# Microcontroller.net
KiCad netlist of a schematic drawn in Altium Designer
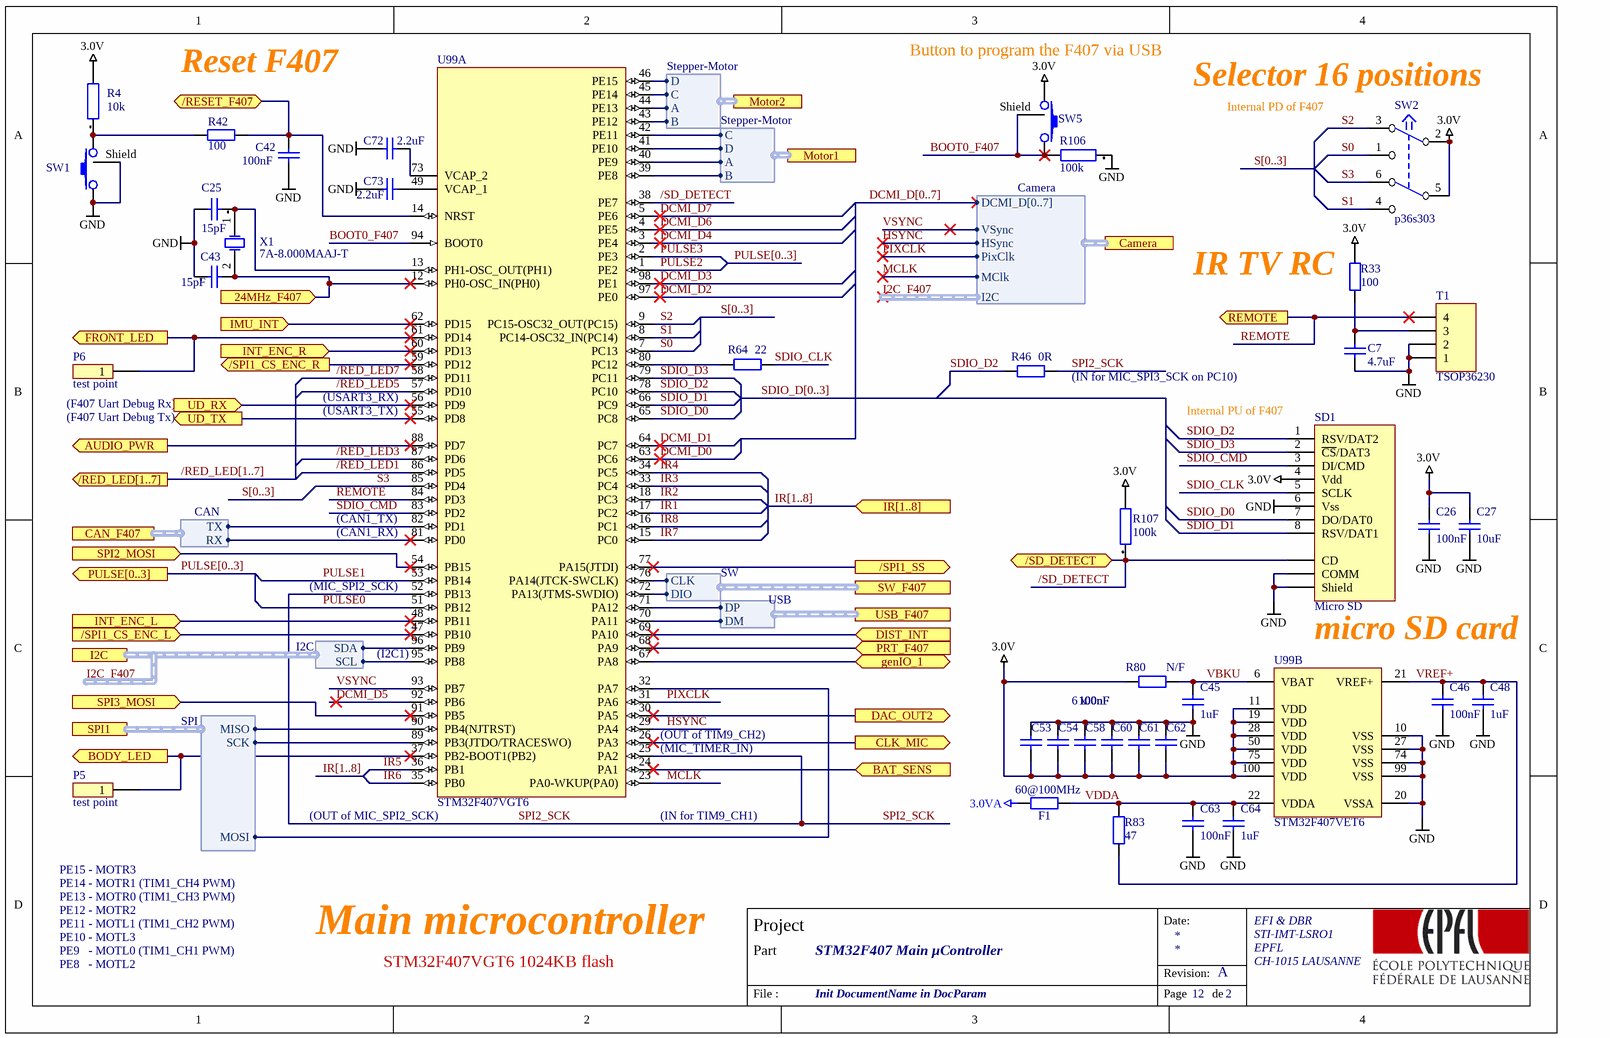
[diagram p0: Microcontroller.SchDoc]

(export (version "E")
  (design (tool "Eeschema 10.0.6"))
  (components
    (comp (ref "C7")
      (value "4.7uF")
      (footprint "ROB_0603")
      (description "Capacitor")
      (fields (field (name "PUBLISHER") "Altium Limited"))
      (libsource (lib "Miscellaneous Devices") (part "Cap"))
    )
    (comp (ref "C25")
      (value "15pF")
      (footprint "ROB_0603")
      (description "Capacitor")
      (fields (field (name "MANUFACTURER") "Phycomp") (field (name "VOLTAGE") "50"))
      (libsource (lib "LSRO1Altium") (part "CAP-NP"))
    )
    (comp (ref "C26")
      (value "100nF")
      (footprint "ROB_0603")
      (description "Capacitor")
      (fields (field (name "PUBLISHER") "Altium Limited"))
      (libsource (lib "Rob_sch") (part "Cap"))
    )
    (comp (ref "C27")
      (value "10uF")
      (footprint "ROB_0603")
      (description "Capacitor")
      (fields (field (name "PUBLISHER") "Altium Limited"))
      (libsource (lib "Rob_sch") (part "Cap"))
    )
    (comp (ref "C42")
      (value "100nF")
      (footprint "ROB_0603")
      (description "Capacitor")
      (fields (field (name "PUBLISHER") "Altium Limited"))
      (libsource (lib "Rob_sch") (part "Cap"))
    )
    (comp (ref "C43")
      (value "15pF")
      (footprint "ROB_0603")
      (description "Capacitor")
      (fields (field (name "MANUFACTURER") "Phycomp") (field (name "VOLTAGE") "50"))
      (libsource (lib "LSRO1Altium") (part "CAP-NP"))
    )
    (comp (ref "C45")
      (value "1uF")
      (footprint "ROB_0603")
      (description "Capacitor")
      (fields (field (name "PUBLISHER") "Altium Limited"))
      (libsource (lib "Rob_sch") (part "Cap"))
    )
    (comp (ref "C46")
      (value "100nF")
      (footprint "ROB_0603")
      (description "Capacitor")
      (fields (field (name "PUBLISHER") "Altium Limited"))
      (libsource (lib "Rob_sch") (part "Cap"))
    )
    (comp (ref "C48")
      (value "1uF")
      (footprint "ROB_0603")
      (description "Capacitor")
      (fields (field (name "PUBLISHER") "Altium Limited"))
      (libsource (lib "Rob_sch") (part "Cap"))
    )
    (comp (ref "C53")
      (value "100nF")
      (footprint "ROB_0603")
      (description "Capacitor")
      (fields (field (name "PUBLISHER") "Altium Limited"))
      (libsource (lib "Rob_sch") (part "Cap"))
    )
    (comp (ref "C54")
      (value "100nF")
      (footprint "ROB_0603")
      (description "Capacitor")
      (fields (field (name "PUBLISHER") "Altium Limited"))
      (libsource (lib "Rob_sch") (part "Cap"))
    )
    (comp (ref "C58")
      (value "100nF")
      (footprint "ROB_0603")
      (description "Capacitor")
      (fields (field (name "PUBLISHER") "Altium Limited"))
      (libsource (lib "Rob_sch") (part "Cap"))
    )
    (comp (ref "C60")
      (value "100nF")
      (footprint "ROB_0603")
      (description "Capacitor")
      (fields (field (name "PUBLISHER") "Altium Limited"))
      (libsource (lib "Rob_sch") (part "Cap"))
    )
    (comp (ref "C61")
      (value "100nF")
      (footprint "ROB_0603")
      (description "Capacitor")
      (fields (field (name "PUBLISHER") "Altium Limited"))
      (libsource (lib "Rob_sch") (part "Cap"))
    )
    (comp (ref "C62")
      (value "100nF")
      (footprint "ROB_0603")
      (description "Capacitor")
      (fields (field (name "PUBLISHER") "Altium Limited"))
      (libsource (lib "Rob_sch") (part "Cap"))
    )
    (comp (ref "C63")
      (value "100nF")
      (footprint "ROB_0603")
      (description "Capacitor")
      (fields (field (name "PUBLISHER") "Altium Limited"))
      (libsource (lib "Rob_sch") (part "Cap"))
    )
    (comp (ref "C64")
      (value "1uF")
      (footprint "ROB_0603")
      (description "Capacitor")
      (fields (field (name "PUBLISHER") "Altium Limited"))
      (libsource (lib "Rob_sch") (part "Cap"))
    )
    (comp (ref "C72")
      (value "2.2uF")
      (footprint "ROB_0603")
      (description "Capacitor")
      (fields (field (name "PUBLISHER") "Altium Limited"))
      (libsource (lib "Rob_sch") (part "Cap"))
    )
    (comp (ref "C73")
      (value "2.2uF")
      (footprint "ROB_0603")
      (description "Capacitor")
      (fields (field (name "PUBLISHER") "Altium Limited"))
      (libsource (lib "Rob_sch") (part "Cap"))
    )
    (comp (ref "F1")
      (value "60@100MHz")
      (footprint "rob_0603")
      (description "Bead Ferrite")
      (libsource (lib "ASLCommonLibrarySch_1.00") (part "RES_0603"))
    )
    (comp (ref "P5")
      (value "test point")
      (footprint "testpoint")
      (description "Header, 1-Pin,  bottom")
      (fields (field (name "MANUFACTURER") "Generic Components") (field (name "PUBLISHER") "Altium Limited"))
      (libsource (lib "Rob_sch") (part "Header 1"))
    )
    (comp (ref "P6")
      (value "test point")
      (footprint "testpoint")
      (description "Header, 1-Pin,  bottom")
      (fields (field (name "MANUFACTURER") "Generic Components") (field (name "PUBLISHER") "Altium Limited"))
      (libsource (lib "Rob_sch") (part "Header 1"))
    )
    (comp (ref "R4")
      (value "10k")
      (footprint "ROB_0603")
      (description "Resistor")
      (fields (field (name "TOLERANCE") "+/-1") (field (name "MANUFACTURER") "Multicomp"))
      (libsource (lib "LSRO1Altium") (part "RES"))
    )
    (comp (ref "R33")
      (value "100")
      (footprint "ROB_0603")
      (description "Resistor")
      (fields (field (name "PUBLISHER") "Altium Limited"))
      (libsource (lib "") (part "Res2_1"))
    )
    (comp (ref "R42")
      (value "100")
      (footprint "ROB_0603")
      (description "Resistor")
      (fields (field (name "PUBLISHER") "Altium Limited"))
      (libsource (lib "") (part "Res2_1"))
    )
    (comp (ref "R46")
      (value "0R")
      (footprint "ROB_0603")
      (description "Resistor")
      (fields (field (name "PUBLISHER") "Altium Limited"))
      (libsource (lib "Miscellaneous Devices") (part "Res2"))
    )
    (comp (ref "R64")
      (value "22")
      (footprint "ROB_0603")
      (description "Resistor")
      (fields (field (name "PUBLISHER") "Altium Limited"))
      (libsource (lib "Miscellaneous Devices") (part "Res2"))
    )
    (comp (ref "R80")
      (value "N/F")
      (footprint "ROB_0603")
      (description "Resistor")
      (fields (field (name "PUBLISHER") "Altium Limited"))
      (libsource (lib "Miscellaneous Devices") (part "Res2"))
    )
    (comp (ref "R83")
      (value "47")
      (footprint "ROB_0603")
      (description "Resistor")
      (fields (field (name "PUBLISHER") "Altium Limited"))
      (libsource (lib "") (part "Res2_2"))
    )
    (comp (ref "R106")
      (value "100k")
      (footprint "ROB_0603")
      (description "Resistor")
      (fields (field (name "TOLERANCE") "+/-1") (field (name "MANUFACTURER") "Multicomp"))
      (libsource (lib "LSRO1Altium") (part "RES"))
    )
    (comp (ref "R107")
      (value "100k")
      (footprint "ROB_0603")
      (description "Resistor")
      (fields (field (name "TOLERANCE") "+/-1") (field (name "MANUFACTURER") "Multicomp"))
      (libsource (lib "LSRO1Altium") (part "RES"))
    )
    (comp (ref "SD1")
      (value "Micro SD")
      (footprint "MicroSD_DM3AT-SF-PEJM5")
      (description "uSD Connector HRS DM3AT-SF-PEJM5")
      (fields (field (name "MANUFACTURER") "Generic Components") (field (name "PUBLISHER") "Altium Limited"))
      (libsource (lib "Rob_sch") (part "CON Micro SD DM3AT-SF-PEJM5"))
    )
    (comp (ref "SW1")
      (value "button")
      (footprint "C&K_KMR2")
      (description "KMR221GLFS")
      (fields (field (name "MANUFACTURER") "Tyco"))
      (libsource (lib "Dev_Card_Lib") (part "C&K KMR2"))
    )
    (comp (ref "SW2")
      (value "p36s303")
      (footprint "p36s")
      (description "hex selector")
      (libsource (lib "Perso_sch") (part "MB2061"))
    )
    (comp (ref "SW5")
      (value "button")
      (footprint "C&K_KMR2")
      (description "KMR221GLFS")
      (fields (field (name "MANUFACTURER") "Tyco"))
      (libsource (lib "Dev_Card_Lib") (part "C&K KMR2"))
    )
    (comp (ref "T1")
      (value "TSOP36230")
      (footprint "TSOP36230")
      (description "IT TV receiver")
      (fields (field (name "PUBLISHER") "Altium Limited"))
      (libsource (lib "Miscellaneous Connectors") (part "Header 4"))
    )
    (comp (ref "U99")
      (value "STM32F407VGT6")
      (footprint "STM-LQFP100_N")
      (fields (field (name "MANUFACTURER") "STMicroelectronics") (field (name "PARTNUMBER") "STM32F407VET6"))
      (libsource (lib "") (part "STM32F407VET6_1"))
    )
    (comp (ref "X1")
      (value "7A-8.000MAAJ-T")
      (footprint "Crystal 8MHz 3.2x5mm-7A-8.000MAAJ-T")
      (description "CRYSTAL 8.0000MHZ 18PF SMD")
      (fields
        (field (name "MANUFACTURER") "TXC CORPORATION")
        (field (name "MANUFACTURER PART NUMBER") "7A-8.000MAAJ-T*")
      )
      (libsource (lib "Dev_Card_Lib") (part "7A-8.000MAAJ-T"))
    )
  )
  (nets
    (net (code "16") (name "/24MHz_F407") (class "Default")
      (node (ref "C43") (pin "2") (pinfunction "2_2") (pintype "passive"))
      (node (ref "U99") (pin "12") (pinfunction "PH0-OSC_IN(PH0)_12") (pintype "bidirectional"))
      (node (ref "X1") (pin "2") (pinfunction "OSC2_2") (pintype "passive"))
    )
    (net (code "17") (name "/AUDIO_PWR") (class "Default")
      (node (ref "U99") (pin "88") (pinfunction "PD7_88") (pintype "bidirectional+no_connect"))
    )
    (net (code "18") (name "/BAT_SENS") (class "Default")
      (node (ref "U99") (pin "24") (pinfunction "PA1_24") (pintype "bidirectional+no_connect"))
    )
    (net (code "19") (name "/BODY_LED") (class "Default")
      (node (ref "P5") (pin "1") (pinfunction "1_1") (pintype "passive"))
      (node (ref "U99") (pin "37") (pinfunction "PB2-BOOT1(PB2)_37") (pintype "bidirectional"))
    )
    (net (code "20") (name "/BOOT0_F407") (class "Default")
      (node (ref "R106") (pin "2") (pinfunction "2_2") (pintype "passive"))
      (node (ref "SW5") (pin "1") (pintype "passive"))
      (node (ref "SW5") (pin "Shield") (pinfunction "Shield_Shield") (pintype "passive"))
      (node (ref "U99") (pin "94") (pinfunction "BOOT0_94") (pintype "input"))
    )
    (net (code "21") (name "/CLK") (class "Default")
      (node (ref "U99") (pin "76") (pinfunction "PA14(JTCK-SWCLK)_76") (pintype "bidirectional"))
    )
    (net (code "22") (name "/CLK_MIC") (class "Default")
      (node (ref "U99") (pin "26") (pinfunction "PA3_26") (pintype "bidirectional+no_connect"))
    )
    (net (code "24") (name "/DAC_OUT2") (class "Default")
      (node (ref "U99") (pin "30") (pinfunction "PA5_30") (pintype "bidirectional+no_connect"))
    )
    (net (code "33") (name "/DCMI_D0") (class "Default")
      (node (ref "U99") (pin "63") (pinfunction "PC6_63") (pintype "bidirectional"))
    )
    (net (code "34") (name "/DCMI_D1") (class "Default")
      (node (ref "U99") (pin "64") (pinfunction "PC7_64") (pintype "bidirectional"))
    )
    (net (code "35") (name "/DCMI_D2") (class "Default")
      (node (ref "U99") (pin "97") (pinfunction "PE0_97") (pintype "bidirectional"))
    )
    (net (code "36") (name "/DCMI_D3") (class "Default")
      (node (ref "U99") (pin "98") (pinfunction "PE1_98") (pintype "bidirectional"))
    )
    (net (code "37") (name "/DCMI_D4") (class "Default")
      (node (ref "U99") (pin "3") (pinfunction "PE4_3") (pintype "bidirectional"))
    )
    (net (code "38") (name "/DCMI_D5") (class "Default")
      (node (ref "U99") (pin "92") (pinfunction "PB6_92") (pintype "bidirectional"))
    )
    (net (code "40") (name "/DCMI_D6") (class "Default")
      (node (ref "U99") (pin "4") (pinfunction "PE5_4") (pintype "bidirectional"))
    )
    (net (code "41") (name "/DCMI_D7") (class "Default")
      (node (ref "U99") (pin "5") (pinfunction "PE6_5") (pintype "bidirectional"))
    )
    (net (code "42") (name "/DIO") (class "Default")
      (node (ref "U99") (pin "72") (pinfunction "PA13(JTMS-SWDIO)_72") (pintype "bidirectional"))
    )
    (net (code "43") (name "/DIST_INT") (class "Default")
      (node (ref "U99") (pin "69") (pinfunction "PA10_69") (pintype "bidirectional+no_connect"))
    )
    (net (code "44") (name "/DM") (class "Default")
      (node (ref "U99") (pin "70") (pinfunction "PA11_70") (pintype "bidirectional"))
    )
    (net (code "45") (name "/DP") (class "Default")
      (node (ref "U99") (pin "71") (pinfunction "PA12_71") (pintype "bidirectional"))
    )
    (net (code "46") (name "/FRONT_LED") (class "Default")
      (node (ref "P6") (pin "1") (pinfunction "1_1") (pintype "passive"))
      (node (ref "U99") (pin "61") (pinfunction "PD14_61") (pintype "bidirectional"))
    )
    (net (code "47") (name "/HSYNC") (class "Default")
      (node (ref "U99") (pin "29") (pinfunction "PA4_29") (pintype "bidirectional+no_connect"))
    )
    (net (code "48") (name "/IMU_INT") (class "Default")
      (node (ref "U99") (pin "62") (pinfunction "PD15_62") (pintype "bidirectional+no_connect"))
    )
    (net (code "49") (name "/INT_ENC_L") (class "Default")
      (node (ref "U99") (pin "48") (pinfunction "PB11_48") (pintype "bidirectional+no_connect"))
    )
    (net (code "50") (name "/INT_ENC_R") (class "Default")
      (node (ref "U99") (pin "60") (pinfunction "PD13_60") (pintype "bidirectional+no_connect"))
    )
    (net (code "52") (name "/IR1") (class "Default")
      (node (ref "U99") (pin "17") (pinfunction "PC2_17") (pintype "bidirectional"))
    )
    (net (code "53") (name "/IR2") (class "Default")
      (node (ref "U99") (pin "18") (pinfunction "PC3_18") (pintype "bidirectional"))
    )
    (net (code "54") (name "/IR3") (class "Default")
      (node (ref "U99") (pin "33") (pinfunction "PC4_33") (pintype "bidirectional"))
    )
    (net (code "55") (name "/IR4") (class "Default")
      (node (ref "U99") (pin "34") (pinfunction "PC5_34") (pintype "bidirectional"))
    )
    (net (code "56") (name "/IR5") (class "Default")
      (node (ref "U99") (pin "36") (pinfunction "PB1_36") (pintype "bidirectional"))
    )
    (net (code "57") (name "/IR6") (class "Default")
      (node (ref "U99") (pin "35") (pinfunction "PB0_35") (pintype "bidirectional"))
    )
    (net (code "58") (name "/IR7") (class "Default")
      (node (ref "U99") (pin "15") (pinfunction "PC0_15") (pintype "bidirectional"))
    )
    (net (code "59") (name "/IR8") (class "Default")
      (node (ref "U99") (pin "16") (pinfunction "PC1_16") (pintype "bidirectional"))
    )
    (net (code "60") (name "/MCLK") (class "Default")
      (node (ref "U99") (pin "23") (pinfunction "PA0-WKUP(PA0)_23") (pintype "bidirectional+no_connect"))
    )
    (net (code "62") (name "/MISO") (class "Default")
      (node (ref "U99") (pin "90") (pinfunction "PB4(NJTRST)_90") (pintype "bidirectional"))
    )
    (net (code "63") (name "/MOSI") (class "Default")
      (node (ref "U99") (pin "32") (pinfunction "PA7_32") (pintype "bidirectional"))
    )
    (net (code "64") (name "/PIXCLK") (class "Default")
      (node (ref "U99") (pin "31") (pinfunction "PA6_31") (pintype "bidirectional+no_connect"))
    )
    (net (code "65") (name "/PRT_F407") (class "Default")
      (node (ref "U99") (pin "68") (pinfunction "PA9_68") (pintype "bidirectional+no_connect"))
    )
    (net (code "66") (name "/PULSE0") (class "Default")
      (node (ref "U99") (pin "51") (pinfunction "PB12_51") (pintype "bidirectional"))
    )
    (net (code "67") (name "/PULSE1") (class "Default")
      (node (ref "U99") (pin "53") (pinfunction "PB14_53") (pintype "bidirectional"))
    )
    (net (code "68") (name "/PULSE2") (class "Default")
      (node (ref "U99") (pin "1") (pinfunction "PE2_1") (pintype "bidirectional"))
    )
    (net (code "69") (name "/PULSE3") (class "Default")
      (node (ref "U99") (pin "2") (pinfunction "PE3_2") (pintype "bidirectional"))
    )
    (net (code "70") (name "/REMOTE") (class "Default")
      (node (ref "T1") (pin "4") (pinfunction "4_4") (pintype "passive"))
      (node (ref "U99") (pin "84") (pinfunction "PD3_84") (pintype "bidirectional"))
    )
    (net (code "71") (name "/RX") (class "Default")
      (node (ref "U99") (pin "81") (pinfunction "PD0_81") (pintype "bidirectional+no_connect"))
    )
    (net (code "72") (name "/S0") (class "Default")
      (node (ref "SW2") (pin "1") (pinfunction "NO1_1") (pintype "passive"))
      (node (ref "U99") (pin "7") (pinfunction "PC13_7") (pintype "bidirectional"))
    )
    (net (code "73") (name "/S1") (class "Default")
      (node (ref "SW2") (pin "4") (pinfunction "NO2_4") (pintype "passive"))
      (node (ref "U99") (pin "8") (pinfunction "PC14-OSC32_IN(PC14)_8") (pintype "bidirectional"))
    )
    (net (code "74") (name "/S2") (class "Default")
      (node (ref "SW2") (pin "3") (pinfunction "NC1_3") (pintype "passive"))
      (node (ref "U99") (pin "9") (pinfunction "PC15-OSC32_OUT(PC15)_9") (pintype "bidirectional"))
    )
    (net (code "75") (name "/S3") (class "Default")
      (node (ref "SW2") (pin "6") (pinfunction "NC2_6") (pintype "passive"))
      (node (ref "U99") (pin "85") (pinfunction "PD4_85") (pintype "bidirectional"))
    )
    (net (code "76") (name "/SCK") (class "Default")
      (node (ref "U99") (pin "89") (pinfunction "PB3(JTDO/TRACESWO)_89") (pintype "bidirectional"))
    )
    (net (code "78") (name "/SCL") (class "Default")
      (node (ref "U99") (pin "95") (pinfunction "PB8_95") (pintype "bidirectional"))
    )
    (net (code "79") (name "/SDA") (class "Default")
      (node (ref "U99") (pin "96") (pinfunction "PB9_96") (pintype "bidirectional"))
    )
    (net (code "80") (name "/SDIO_CLK") (class "Default")
      (node (ref "R64") (pin "1") (pinfunction "1_1") (pintype "passive"))
      (node (ref "SD1") (pin "5") (pinfunction "SCLK_5") (pintype "passive"))
    )
    (net (code "82") (name "/SDIO_CMD") (class "Default")
      (node (ref "SD1") (pin "3") (pinfunction "DI/CMD_3") (pintype "passive"))
      (node (ref "U99") (pin "83") (pinfunction "PD2_83") (pintype "bidirectional"))
    )
    (net (code "83") (name "/SDIO_D0") (class "Default")
      (node (ref "SD1") (pin "7") (pinfunction "DO/DAT0_7") (pintype "passive"))
      (node (ref "U99") (pin "65") (pinfunction "PC8_65") (pintype "bidirectional"))
    )
    (net (code "84") (name "/SDIO_D1") (class "Default")
      (node (ref "SD1") (pin "8") (pinfunction "RSV/DAT1_8") (pintype "passive"))
      (node (ref "U99") (pin "66") (pinfunction "PC9_66") (pintype "bidirectional"))
    )
    (net (code "85") (name "/SDIO_D2") (class "Default")
      (node (ref "R46") (pin "2") (pinfunction "2_2") (pintype "passive"))
      (node (ref "SD1") (pin "1") (pinfunction "RSV/DAT2_1") (pintype "passive"))
      (node (ref "U99") (pin "78") (pinfunction "PC10_78") (pintype "bidirectional"))
    )
    (net (code "86") (name "/SDIO_D3") (class "Default")
      (node (ref "SD1") (pin "2") (pinfunction "~{CS}/DAT3_2") (pintype "passive"))
      (node (ref "U99") (pin "79") (pinfunction "PC11_79") (pintype "bidirectional"))
    )
    (net (code "87") (name "/SPI2_MOSI") (class "Default")
      (node (ref "U99") (pin "54") (pinfunction "PB15_54") (pintype "bidirectional+no_connect"))
    )
    (net (code "88") (name "/SPI2_SCK") (class "Default")
      (node (ref "R46") (pin "1") (pinfunction "1_1") (pintype "passive"))
      (node (ref "U99") (pin "25") (pinfunction "PA2_25") (pintype "bidirectional"))
      (node (ref "U99") (pin "52") (pinfunction "PB13_52") (pintype "bidirectional"))
    )
    (net (code "89") (name "/SPI3_MOSI") (class "Default")
      (node (ref "U99") (pin "91") (pinfunction "PB5_91") (pintype "bidirectional+no_connect"))
    )
    (net (code "97") (name "/TX") (class "Default")
      (node (ref "U99") (pin "82") (pinfunction "PD1_82") (pintype "bidirectional"))
    )
    (net (code "98") (name "/UD_RX") (class "Default")
      (node (ref "U99") (pin "56") (pinfunction "PD9_56") (pintype "bidirectional+no_connect"))
    )
    (net (code "99") (name "/UD_TX") (class "Default")
      (node (ref "U99") (pin "55") (pinfunction "PD8_55") (pintype "bidirectional+no_connect"))
    )
    (net (code "100") (name "/VBKU") (class "Default")
      (node (ref "C45") (pin "2") (pinfunction "2_2") (pintype "passive"))
      (node (ref "R80") (pin "1") (pinfunction "1_1") (pintype "passive"))
      (node (ref "U99") (pin "6") (pinfunction "VBAT_6") (pintype "power_in"))
    )
    (net (code "102") (name "/VDDA") (class "Default")
      (node (ref "C63") (pin "2") (pinfunction "2_2") (pintype "passive"))
      (node (ref "C64") (pin "2") (pinfunction "2_2") (pintype "passive"))
      (node (ref "F1") (pin "2") (pinfunction "2_2") (pintype "passive"))
      (node (ref "R83") (pin "1") (pinfunction "1_1") (pintype "passive"))
      (node (ref "U99") (pin "22") (pinfunction "VDDA_22") (pintype "power_in"))
    )
    (net (code "103") (name "/VREF+") (class "Default")
      (node (ref "C46") (pin "2") (pinfunction "2_2") (pintype "passive"))
      (node (ref "C48") (pin "2") (pinfunction "2_2") (pintype "passive"))
      (node (ref "R83") (pin "2") (pinfunction "2_2") (pintype "passive"))
      (node (ref "U99") (pin "21") (pinfunction "VREF+_21") (pintype "power_in"))
    )
    (net (code "104") (name "/VSYNC") (class "Default")
      (node (ref "U99") (pin "93") (pinfunction "PB7_93") (pintype "bidirectional"))
    )
    (net (code "105") (name "/genIO_1") (class "Default")
      (node (ref "U99") (pin "67") (pinfunction "PA8_67") (pintype "bidirectional"))
    )
    (net (code "106") (name "/{slash}RED_LED1") (class "Default")
      (node (ref "U99") (pin "86") (pinfunction "PD5_86") (pintype "bidirectional"))
    )
    (net (code "107") (name "/{slash}RED_LED3") (class "Default")
      (node (ref "U99") (pin "87") (pinfunction "PD6_87") (pintype "bidirectional"))
    )
    (net (code "108") (name "/{slash}RED_LED5") (class "Default")
      (node (ref "U99") (pin "57") (pinfunction "PD10_57") (pintype "bidirectional"))
    )
    (net (code "109") (name "/{slash}RED_LED7") (class "Default")
      (node (ref "U99") (pin "58") (pinfunction "PD11_58") (pintype "bidirectional"))
    )
    (net (code "110") (name "/{slash}RESET_F407") (class "Default")
      (node (ref "C42") (pin "1") (pinfunction "1_1") (pintype "passive"))
      (node (ref "R42") (pin "2") (pinfunction "2_2") (pintype "passive"))
      (node (ref "U99") (pin "14") (pinfunction "NRST_14") (pintype "bidirectional"))
    )
    (net (code "111") (name "/{slash}SD_DETECT") (class "Default")
      (node (ref "R107") (pin "1") (pinfunction "1_1") (pintype "passive"))
      (node (ref "SD1") (pin "CD") (pinfunction "CD_CD") (pintype "passive"))
      (node (ref "U99") (pin "38") (pinfunction "PE7_38") (pintype "bidirectional"))
    )
    (net (code "112") (name "/{slash}SPI1_CS_ENC_L") (class "Default")
      (node (ref "U99") (pin "47") (pinfunction "PB10_47") (pintype "bidirectional+no_connect"))
    )
    (net (code "113") (name "/{slash}SPI1_CS_ENC_R") (class "Default")
      (node (ref "U99") (pin "59") (pinfunction "PD12_59") (pintype "bidirectional+no_connect"))
    )
    (net (code "114") (name "/{slash}SPI1_SS") (class "Default")
      (node (ref "U99") (pin "77") (pinfunction "PA15(JTDI)_77") (pintype "bidirectional+no_connect"))
    )
    (net (code "115") (name "3.0V") (class "Default")
      (node (ref "C26") (pin "2") (pinfunction "2_2") (pintype "passive"))
      (node (ref "C27") (pin "2") (pinfunction "2_2") (pintype "passive"))
      (node (ref "C53") (pin "1") (pinfunction "1_1") (pintype "passive"))
      (node (ref "C54") (pin "1") (pinfunction "1_1") (pintype "passive"))
      (node (ref "C58") (pin "1") (pinfunction "1_1") (pintype "passive"))
      (node (ref "C60") (pin "1") (pinfunction "1_1") (pintype "passive"))
      (node (ref "C61") (pin "1") (pinfunction "1_1") (pintype "passive"))
      (node (ref "C62") (pin "1") (pinfunction "1_1") (pintype "passive"))
      (node (ref "R107") (pin "2") (pinfunction "2_2") (pintype "passive"))
      (node (ref "R33") (pin "2") (pinfunction "2_2") (pintype "passive"))
      (node (ref "R4") (pin "2") (pinfunction "2_2") (pintype "passive"))
      (node (ref "R80") (pin "2") (pinfunction "2_2") (pintype "passive"))
      (node (ref "SD1") (pin "4") (pinfunction "Vdd_4") (pintype "passive"))
      (node (ref "SW2") (pin "2") (pinfunction "COM1_2") (pintype "passive"))
      (node (ref "SW2") (pin "5") (pinfunction "COM2_5") (pintype "passive"))
      (node (ref "SW5") (pin "2") (pintype "passive"))
      (node (ref "U99") (pin "100") (pinfunction "VDD_100") (pintype "power_in"))
      (node (ref "U99") (pin "11") (pinfunction "VDD_11") (pintype "power_in"))
      (node (ref "U99") (pin "19") (pinfunction "VDD_19") (pintype "power_in"))
      (node (ref "U99") (pin "28") (pinfunction "VDD_28") (pintype "power_in"))
      (node (ref "U99") (pin "50") (pinfunction "VDD_50") (pintype "power_in"))
      (node (ref "U99") (pin "75") (pinfunction "VDD_75") (pintype "power_in"))
    )
    (net (code "116") (name "3.0VA") (class "Default")
      (node (ref "F1") (pin "1") (pinfunction "1_1") (pintype "passive"))
    )
    (net (code "117") (name "GND") (class "Default")
      (node (ref "C25") (pin "2") (pinfunction "2_2") (pintype "passive"))
      (node (ref "C26") (pin "1") (pinfunction "1_1") (pintype "passive"))
      (node (ref "C27") (pin "1") (pinfunction "1_1") (pintype "passive"))
      (node (ref "C42") (pin "2") (pinfunction "2_2") (pintype "passive"))
      (node (ref "C43") (pin "1") (pinfunction "1_1") (pintype "passive"))
      (node (ref "C45") (pin "1") (pinfunction "1_1") (pintype "passive"))
      (node (ref "C46") (pin "1") (pinfunction "1_1") (pintype "passive"))
      (node (ref "C48") (pin "1") (pinfunction "1_1") (pintype "passive"))
      (node (ref "C53") (pin "2") (pinfunction "2_2") (pintype "passive"))
      (node (ref "C54") (pin "2") (pinfunction "2_2") (pintype "passive"))
      (node (ref "C58") (pin "2") (pinfunction "2_2") (pintype "passive"))
      (node (ref "C60") (pin "2") (pinfunction "2_2") (pintype "passive"))
      (node (ref "C61") (pin "2") (pinfunction "2_2") (pintype "passive"))
      (node (ref "C62") (pin "2") (pinfunction "2_2") (pintype "passive"))
      (node (ref "C63") (pin "1") (pinfunction "1_1") (pintype "passive"))
      (node (ref "C64") (pin "1") (pinfunction "1_1") (pintype "passive"))
      (node (ref "C7") (pin "1") (pinfunction "1_1") (pintype "passive"))
      (node (ref "C72") (pin "2") (pinfunction "2_2") (pintype "passive"))
      (node (ref "C73") (pin "1") (pinfunction "1_1") (pintype "passive"))
      (node (ref "R106") (pin "1") (pinfunction "1_1") (pintype "passive"))
      (node (ref "SD1") (pin "6") (pinfunction "Vss_6") (pintype "passive"))
      (node (ref "SD1") (pin "COMM") (pinfunction "COMM_COMM") (pintype "passive"))
      (node (ref "SD1") (pin "S") (pinfunction "Shield_S") (pintype "passive"))
      (node (ref "SW1") (pin "1") (pintype "passive"))
      (node (ref "SW1") (pin "Shield") (pinfunction "Shield_Shield") (pintype "passive"))
      (node (ref "T1") (pin "1") (pinfunction "1_1") (pintype "passive"))
      (node (ref "T1") (pin "2") (pinfunction "2_2") (pintype "passive"))
      (node (ref "U99") (pin "10") (pinfunction "VSS_10") (pintype "power_in"))
      (node (ref "U99") (pin "20") (pinfunction "VSSA_20") (pintype "power_in"))
      (node (ref "U99") (pin "27") (pinfunction "VSS_27") (pintype "power_in"))
      (node (ref "U99") (pin "74") (pinfunction "VSS_74") (pintype "power_in"))
      (node (ref "U99") (pin "99") (pinfunction "VSS_99") (pintype "power_in"))
    )
    (net (code "118") (name "Net-(C7-Pad2)") (class "Default")
      (node (ref "C7") (pin "2") (pinfunction "2_2") (pintype "passive"))
      (node (ref "R33") (pin "1") (pinfunction "1_1") (pintype "passive"))
      (node (ref "T1") (pin "3") (pinfunction "3_3") (pintype "passive"))
    )
    (net (code "119") (name "Net-(R4-Pad1)") (class "Default")
      (node (ref "R4") (pin "1") (pinfunction "1_1") (pintype "passive"))
      (node (ref "R42") (pin "1") (pinfunction "1_1") (pintype "passive"))
      (node (ref "SW1") (pin "2") (pintype "passive"))
    )
    (net (code "120") (name "Net-(U99A-PC12)") (class "Default")
      (node (ref "R64") (pin "2") (pinfunction "2_2") (pintype "passive"))
      (node (ref "U99") (pin "80") (pinfunction "PC12_80") (pintype "bidirectional"))
    )
    (net (code "121") (name "Net-(U99A-PH1-OSC_OUT(PH1))") (class "Default")
      (node (ref "C25") (pin "1") (pinfunction "1_1") (pintype "passive"))
      (node (ref "U99") (pin "13") (pinfunction "PH1-OSC_OUT(PH1)_13") (pintype "bidirectional"))
      (node (ref "X1") (pin "1") (pinfunction "OSC1_1") (pintype "passive"))
    )
    (net (code "122") (name "Net-(U99A-VCAP_1)") (class "Default")
      (node (ref "C73") (pin "2") (pinfunction "2_2") (pintype "passive"))
      (node (ref "U99") (pin "49") (pinfunction "VCAP_1_49") (pintype "power_in"))
    )
    (net (code "123") (name "Net-(U99A-VCAP_2)") (class "Default")
      (node (ref "C72") (pin "1") (pinfunction "1_1") (pintype "passive"))
      (node (ref "U99") (pin "73") (pinfunction "VCAP_2_73") (pintype "power_in"))
    )
    (net (code "124") (name "unconnected-(U99A-PE8-Pad39)") (class "Default")
      (node (ref "U99") (pin "39") (pinfunction "PE8_39") (pintype "bidirectional"))
    )
    (net (code "125") (name "unconnected-(U99A-PE9-Pad40)") (class "Default")
      (node (ref "U99") (pin "40") (pinfunction "PE9_40") (pintype "bidirectional"))
    )
    (net (code "126") (name "unconnected-(U99A-PE10-Pad41)") (class "Default")
      (node (ref "U99") (pin "41") (pinfunction "PE10_41") (pintype "bidirectional"))
    )
    (net (code "127") (name "unconnected-(U99A-PE11-Pad42)") (class "Default")
      (node (ref "U99") (pin "42") (pinfunction "PE11_42") (pintype "bidirectional"))
    )
    (net (code "128") (name "unconnected-(U99A-PE12-Pad43)") (class "Default")
      (node (ref "U99") (pin "43") (pinfunction "PE12_43") (pintype "bidirectional"))
    )
    (net (code "129") (name "unconnected-(U99A-PE13-Pad44)") (class "Default")
      (node (ref "U99") (pin "44") (pinfunction "PE13_44") (pintype "bidirectional"))
    )
    (net (code "130") (name "unconnected-(U99A-PE14-Pad45)") (class "Default")
      (node (ref "U99") (pin "45") (pinfunction "PE14_45") (pintype "bidirectional"))
    )
    (net (code "131") (name "unconnected-(U99A-PE15-Pad46)") (class "Default")
      (node (ref "U99") (pin "46") (pinfunction "PE15_46") (pintype "bidirectional"))
    )
  )
)
